# HeadMouse_small.net
KiCad netlist of a schematic drawn in EAGLE
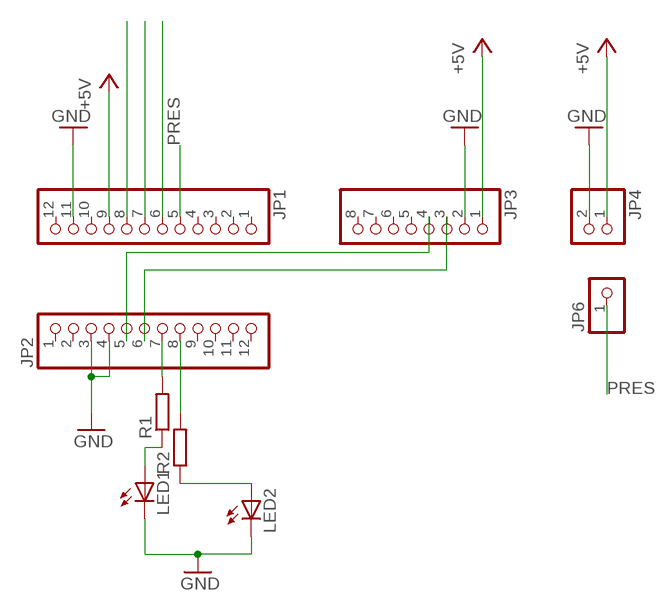
[diagram p0: schematic, sheet 1]

(export (version "E")
  (design (tool "Eeschema 10.0.6"))
  (components
    (comp (ref "JP1")
      (value "PINHD-1X12")
      (footprint "eagle-import:1X12")
      (libsource (lib "eagle-import") (part "PINHD-1X12"))
    )
    (comp (ref "JP2")
      (value "PINHD-1X12")
      (footprint "eagle-import:1X12")
      (libsource (lib "eagle-import") (part "PINHD-1X12"))
    )
    (comp (ref "JP3")
      (value "PINHD-1X8BIG")
      (footprint "eagle-import:1X08-BIG")
      (libsource (lib "eagle-import") (part "PINHD-1X8BIG"))
    )
    (comp (ref "JP4")
      (value "PINHD-1X2")
      (footprint "eagle-import:1X02")
      (libsource (lib "eagle-import") (part "PINHD-1X2"))
    )
    (comp (ref "JP6")
      (value "PINHD-1X1")
      (footprint "eagle-import:1X01")
      (libsource (lib "eagle-import") (part "PINHD-1X1"))
    )
    (comp (ref "LED1")
      (value "LED3MM")
      (footprint "eagle-import:LED3MM")
      (libsource (lib "eagle-import") (part "LED3MM"))
    )
    (comp (ref "LED2")
      (value "LED3MM")
      (footprint "eagle-import:LED3MM")
      (libsource (lib "eagle-import") (part "LED3MM"))
    )
    (comp (ref "R1")
      (value "R-EU_0204/7")
      (footprint "eagle-import:0204_7")
      (libsource (lib "eagle-import") (part "R-EU_0204/7"))
    )
    (comp (ref "R2")
      (value "R-EU_0204/7")
      (footprint "eagle-import:0204_7")
      (libsource (lib "eagle-import") (part "R-EU_0204/7"))
    )
  )
  (nets
    (net (code "1") (name "+5V") (class "Default")
      (node (ref "JP1") (pin "9") (pinfunction "9_9") (pintype "passive"))
      (node (ref "JP3") (pin "1") (pinfunction "1_1") (pintype "passive"))
      (node (ref "JP4") (pin "1") (pinfunction "1_1") (pintype "passive"))
    )
    (net (code "2") (name "/PRES") (class "Default")
      (node (ref "JP1") (pin "5") (pinfunction "5_5") (pintype "passive"))
      (node (ref "JP6") (pin "1") (pinfunction "1_1") (pintype "passive"))
    )
    (net (code "3") (name "GND") (class "Default")
      (node (ref "JP1") (pin "11") (pinfunction "11_11") (pintype "passive"))
      (node (ref "JP2") (pin "3") (pinfunction "3_3") (pintype "passive"))
      (node (ref "JP2") (pin "4") (pinfunction "4_4") (pintype "passive"))
      (node (ref "JP3") (pin "2") (pinfunction "2_2") (pintype "passive"))
      (node (ref "JP4") (pin "2") (pinfunction "2_2") (pintype "passive"))
      (node (ref "LED1") (pin "K") (pinfunction "C_K") (pintype "passive"))
      (node (ref "LED2") (pin "K") (pinfunction "C_K") (pintype "passive"))
    )
    (net (code "4") (name "Net-(JP2-Pad5)") (class "Default")
      (node (ref "JP2") (pin "5") (pinfunction "5_5") (pintype "passive"))
      (node (ref "JP3") (pin "4") (pinfunction "4_4") (pintype "passive"))
    )
    (net (code "5") (name "Net-(JP2-Pad6)") (class "Default")
      (node (ref "JP2") (pin "6") (pinfunction "6_6") (pintype "passive"))
      (node (ref "JP3") (pin "3") (pinfunction "3_3") (pintype "passive"))
    )
    (net (code "6") (name "Net-(JP2-Pad7)") (class "Default")
      (node (ref "JP2") (pin "7") (pinfunction "7_7") (pintype "passive"))
      (node (ref "R1") (pin "2") (pinfunction "2_2") (pintype "passive"))
    )
    (net (code "7") (name "Net-(JP2-Pad8)") (class "Default")
      (node (ref "JP2") (pin "8") (pinfunction "8_8") (pintype "passive"))
      (node (ref "R2") (pin "2") (pinfunction "2_2") (pintype "passive"))
    )
    (net (code "8") (name "Net-(LED1-PadA)") (class "Default")
      (node (ref "LED1") (pin "A") (pinfunction "A_A") (pintype "passive"))
      (node (ref "R1") (pin "1") (pinfunction "1_1") (pintype "passive"))
    )
    (net (code "9") (name "Net-(LED2-PadA)") (class "Default")
      (node (ref "LED2") (pin "A") (pinfunction "A_A") (pintype "passive"))
      (node (ref "R2") (pin "1") (pinfunction "1_1") (pintype "passive"))
    )
    (net (code "10") (name "unconnected-(JP1-Pad1)") (class "Default")
      (node (ref "JP1") (pin "1") (pinfunction "1_1") (pintype "passive"))
    )
    (net (code "11") (name "unconnected-(JP1-Pad2)") (class "Default")
      (node (ref "JP1") (pin "2") (pinfunction "2_2") (pintype "passive"))
    )
    (net (code "12") (name "unconnected-(JP1-Pad3)") (class "Default")
      (node (ref "JP1") (pin "3") (pinfunction "3_3") (pintype "passive"))
    )
    (net (code "13") (name "unconnected-(JP1-Pad4)") (class "Default")
      (node (ref "JP1") (pin "4") (pinfunction "4_4") (pintype "passive"))
    )
    (net (code "14") (name "unconnected-(JP1-Pad6)") (class "Default")
      (node (ref "JP1") (pin "6") (pinfunction "6_6") (pintype "passive"))
    )
    (net (code "15") (name "unconnected-(JP1-Pad7)") (class "Default")
      (node (ref "JP1") (pin "7") (pinfunction "7_7") (pintype "passive"))
    )
    (net (code "16") (name "unconnected-(JP1-Pad8)") (class "Default")
      (node (ref "JP1") (pin "8") (pinfunction "8_8") (pintype "passive"))
    )
    (net (code "17") (name "unconnected-(JP1-Pad10)") (class "Default")
      (node (ref "JP1") (pin "10") (pinfunction "10_10") (pintype "passive"))
    )
    (net (code "18") (name "unconnected-(JP1-Pad12)") (class "Default")
      (node (ref "JP1") (pin "12") (pinfunction "12_12") (pintype "passive"))
    )
    (net (code "19") (name "unconnected-(JP2-Pad1)") (class "Default")
      (node (ref "JP2") (pin "1") (pinfunction "1_1") (pintype "passive"))
    )
    (net (code "20") (name "unconnected-(JP2-Pad2)") (class "Default")
      (node (ref "JP2") (pin "2") (pinfunction "2_2") (pintype "passive"))
    )
    (net (code "21") (name "unconnected-(JP2-Pad9)") (class "Default")
      (node (ref "JP2") (pin "9") (pinfunction "9_9") (pintype "passive"))
    )
    (net (code "22") (name "unconnected-(JP2-Pad10)") (class "Default")
      (node (ref "JP2") (pin "10") (pinfunction "10_10") (pintype "passive"))
    )
    (net (code "23") (name "unconnected-(JP2-Pad11)") (class "Default")
      (node (ref "JP2") (pin "11") (pinfunction "11_11") (pintype "passive"))
    )
    (net (code "24") (name "unconnected-(JP2-Pad12)") (class "Default")
      (node (ref "JP2") (pin "12") (pinfunction "12_12") (pintype "passive"))
    )
    (net (code "25") (name "unconnected-(JP3-Pad5)") (class "Default")
      (node (ref "JP3") (pin "5") (pinfunction "5_5") (pintype "passive"))
    )
    (net (code "26") (name "unconnected-(JP3-Pad6)") (class "Default")
      (node (ref "JP3") (pin "6") (pinfunction "6_6") (pintype "passive"))
    )
    (net (code "27") (name "unconnected-(JP3-Pad7)") (class "Default")
      (node (ref "JP3") (pin "7") (pinfunction "7_7") (pintype "passive"))
    )
    (net (code "28") (name "unconnected-(JP3-Pad8)") (class "Default")
      (node (ref "JP3") (pin "8") (pinfunction "8_8") (pintype "passive"))
    )
  )
)
